# 555_Solar_Wind.net
KiCad netlist of a schematic drawn in EAGLE
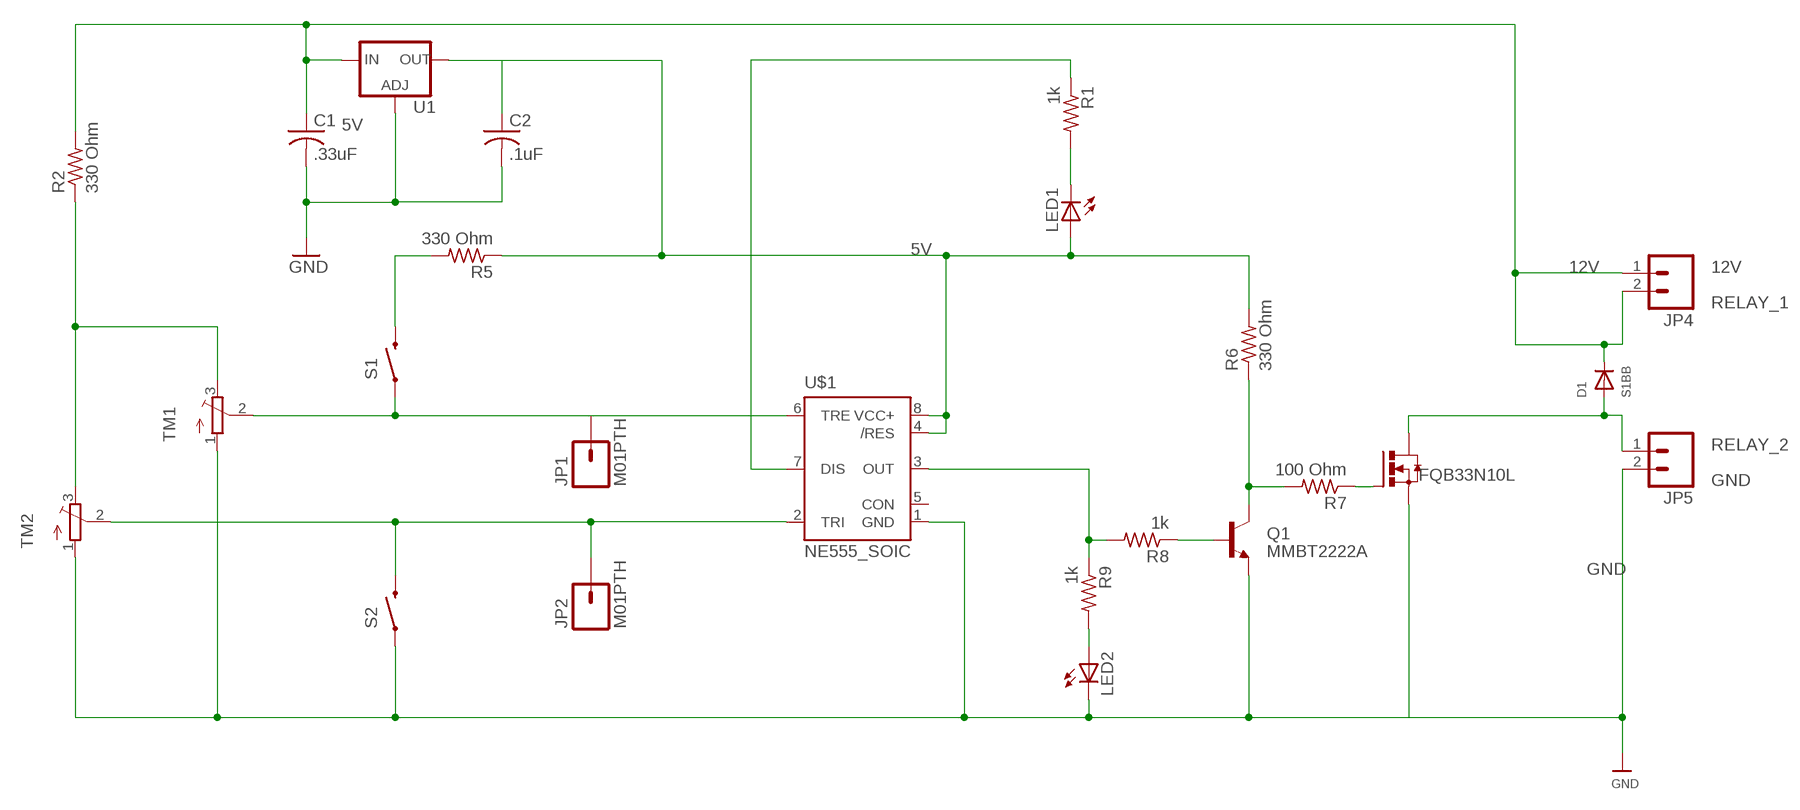
[diagram p0: schematic, sheet 1]

(export (version "E")
  (design (tool "Eeschema 10.0.6"))
  (components
    (comp (ref "C1")
      (value ".33uF")
      (footprint "eagle-import:C0805K")
      (libsource (lib "eagle-import") (part "C-USC0805K"))
    )
    (comp (ref "C2")
      (value ".1uF")
      (footprint "eagle-import:C0805K")
      (libsource (lib "eagle-import") (part "C-USC0805K"))
    )
    (comp (ref "D1")
      (value "S1BB")
      (footprint "eagle-import:SMADIODE")
      (libsource (lib "eagle-import") (part "DIODESMA"))
    )
    (comp (ref "JP1")
      (value "M01PTH")
      (footprint "eagle-import:1X01")
      (libsource (lib "eagle-import") (part "M01PTH"))
    )
    (comp (ref "JP2")
      (value "M01PTH")
      (footprint "eagle-import:1X01")
      (libsource (lib "eagle-import") (part "M01PTH"))
    )
    (comp (ref "JP4")
      (value "M023.5MM_LOCK")
      (footprint "eagle-import:SCREWTERMINAL-3.5MM-2_LOCK")
      (libsource (lib "eagle-import") (part "M023.5MM_LOCK"))
    )
    (comp (ref "JP5")
      (value "M023.5MM_LOCK")
      (footprint "eagle-import:SCREWTERMINAL-3.5MM-2_LOCK")
      (libsource (lib "eagle-import") (part "M023.5MM_LOCK"))
    )
    (comp (ref "LED1")
      (value "LEDCHIP-LED0603")
      (footprint "eagle-import:CHIP-LED0603")
      (libsource (lib "eagle-import") (part "LEDCHIP-LED0603"))
    )
    (comp (ref "LED2")
      (value "LEDCHIP-LED0603")
      (footprint "eagle-import:CHIP-LED0603")
      (libsource (lib "eagle-import") (part "LEDCHIP-LED0603"))
    )
    (comp (ref "Q1")
      (value "MMBT2222A")
      (footprint "eagle-import:SOT23")
      (libsource (lib "eagle-import") (part "TRANSISTOR_NPNMMBT2222A"))
    )
    (comp (ref "Q2")
      (value "FQB33N10L")
      (footprint "eagle-import:D2PACK")
      (libsource (lib "eagle-import") (part "IRF3704S"))
    )
    (comp (ref "R1")
      (value "1k")
      (footprint "eagle-import:M0805")
      (libsource (lib "eagle-import") (part "R-US_M0805"))
    )
    (comp (ref "R2")
      (value "330 Ohm")
      (footprint "eagle-import:M0805")
      (libsource (lib "eagle-import") (part "R-US_M0805"))
    )
    (comp (ref "R5")
      (value "330 Ohm")
      (footprint "eagle-import:M0805")
      (libsource (lib "eagle-import") (part "R-US_M0805"))
    )
    (comp (ref "R6")
      (value "330 Ohm")
      (footprint "eagle-import:M0805")
      (libsource (lib "eagle-import") (part "R-US_M0805"))
    )
    (comp (ref "R7")
      (value "100 Ohm")
      (footprint "eagle-import:M0805")
      (libsource (lib "eagle-import") (part "R-US_M0805"))
    )
    (comp (ref "R8")
      (value "1k")
      (footprint "eagle-import:M0805")
      (libsource (lib "eagle-import") (part "R-US_M0805"))
    )
    (comp (ref "R9")
      (value "1k")
      (footprint "eagle-import:M0805")
      (libsource (lib "eagle-import") (part "R-US_M0805"))
    )
    (comp (ref "S1")
      (value "SWITCH-MOMENTARY-2")
      (footprint "eagle-import:TACTILE_SWITCH_TALL")
      (libsource (lib "eagle-import") (part "SWITCH-MOMENTARY-2"))
    )
    (comp (ref "S2")
      (value "SWITCH-MOMENTARY-2")
      (footprint "eagle-import:TACTILE_SWITCH_TALL")
      (libsource (lib "eagle-import") (part "SWITCH-MOMENTARY-2"))
    )
    (comp (ref "TM1")
      (value "TRIMPOTTC33X")
      (footprint "eagle-import:TC33X")
      (libsource (lib "eagle-import") (part "TRIMPOTTC33X"))
    )
    (comp (ref "TM2")
      (value "TRIMPOTTC33X")
      (footprint "eagle-import:TC33X")
      (libsource (lib "eagle-import") (part "TRIMPOTTC33X"))
    )
    (comp (ref "U$1")
      (value "NE555_SOIC")
      (footprint "eagle-import:SO08")
      (libsource (lib "eagle-import") (part "NE555_SOIC"))
    )
    (comp (ref "U1")
      (value "5V")
      (footprint "eagle-import:SOT223")
      (libsource (lib "eagle-import") (part "V_REG_317SMD"))
    )
  )
  (nets
    (net (code "1") (name "/5V") (class "Default")
      (node (ref "C2") (pin "1") (pinfunction "1_1") (pintype "passive"))
      (node (ref "LED1") (pin "A") (pinfunction "A_A") (pintype "passive"))
      (node (ref "R5") (pin "1") (pinfunction "1_1") (pintype "passive"))
      (node (ref "R6") (pin "2") (pinfunction "2_2") (pintype "passive"))
      (node (ref "U$1") (pin "4") (pinfunction "/RES_4") (pintype "input"))
      (node (ref "U$1") (pin "8") (pinfunction "VCC+_8") (pintype "power_in"))
      (node (ref "U1") (pin "2") (pinfunction "OUT_2") (pintype "output"))
    )
    (net (code "2") (name "/12V") (class "Default")
      (node (ref "C1") (pin "1") (pinfunction "1_1") (pintype "passive"))
      (node (ref "D1") (pin "C") (pinfunction "C_C") (pintype "passive"))
      (node (ref "JP4") (pin "1") (pinfunction "1_1") (pintype "passive"))
      (node (ref "JP4") (pin "2") (pinfunction "2_2") (pintype "passive"))
      (node (ref "R2") (pin "2") (pinfunction "2_2") (pintype "passive"))
      (node (ref "U1") (pin "3") (pinfunction "IN_3") (pintype "input"))
    )
    (net (code "3") (name "GND") (class "Default")
      (node (ref "C1") (pin "2") (pinfunction "2_2") (pintype "passive"))
      (node (ref "C2") (pin "2") (pinfunction "2_2") (pintype "passive"))
      (node (ref "JP5") (pin "2") (pinfunction "2_2") (pintype "passive"))
      (node (ref "LED2") (pin "C") (pinfunction "C_C") (pintype "passive"))
      (node (ref "Q1") (pin "2") (pinfunction "E_2") (pintype "passive"))
      (node (ref "Q2") (pin "3") (pinfunction "S_3") (pintype "passive"))
      (node (ref "S2") (pin "A2") (pinfunction "1_A2") (pintype "passive"))
      (node (ref "TM1") (pin "1") (pinfunction "A_1") (pintype "passive"))
      (node (ref "TM2") (pin "1") (pinfunction "A_1") (pintype "passive"))
      (node (ref "U$1") (pin "1") (pinfunction "GND_1") (pintype "power_in"))
      (node (ref "U1") (pin "1") (pinfunction "ADJ_1") (pintype "input"))
    )
    (net (code "4") (name "Net-(LED1-PadC)") (class "Default")
      (node (ref "LED1") (pin "C") (pinfunction "C_C") (pintype "passive"))
      (node (ref "R1") (pin "2") (pinfunction "2_2") (pintype "passive"))
    )
    (net (code "5") (name "Net-(LED2-PadA)") (class "Default")
      (node (ref "LED2") (pin "A") (pinfunction "A_A") (pintype "passive"))
      (node (ref "R9") (pin "2") (pinfunction "2_2") (pintype "passive"))
    )
    (net (code "6") (name "Net-(Q1-B)") (class "Default")
      (node (ref "Q1") (pin "1") (pinfunction "B_1") (pintype "passive"))
      (node (ref "R8") (pin "1") (pinfunction "1_1") (pintype "passive"))
    )
    (net (code "7") (name "Net-(Q1-C)") (class "Default")
      (node (ref "Q1") (pin "3") (pinfunction "C_3") (pintype "passive"))
      (node (ref "R6") (pin "1") (pinfunction "1_1") (pintype "passive"))
      (node (ref "R7") (pin "2") (pinfunction "2_2") (pintype "passive"))
    )
    (net (code "8") (name "Net-(Q2-D)") (class "Default")
      (node (ref "D1") (pin "A") (pinfunction "A_A") (pintype "passive"))
      (node (ref "JP5") (pin "1") (pinfunction "1_1") (pintype "passive"))
      (node (ref "Q2") (pin "2") (pinfunction "D_2") (pintype "passive"))
    )
    (net (code "9") (name "Net-(Q2-G)") (class "Default")
      (node (ref "Q2") (pin "1") (pinfunction "G_1") (pintype "passive"))
      (node (ref "R7") (pin "1") (pinfunction "1_1") (pintype "passive"))
    )
    (net (code "10") (name "Net-(S1-1)") (class "Default")
      (node (ref "JP1") (pin "1") (pinfunction "1_1") (pintype "passive"))
      (node (ref "S1") (pin "A2") (pinfunction "1_A2") (pintype "passive"))
      (node (ref "TM1") (pin "2") (pinfunction "S_2") (pintype "passive"))
      (node (ref "U$1") (pin "6") (pinfunction "TRE_6") (pintype "input"))
    )
    (net (code "11") (name "Net-(S1-2)") (class "Default")
      (node (ref "R5") (pin "2") (pinfunction "2_2") (pintype "passive"))
      (node (ref "S1") (pin "B2") (pinfunction "2_B2") (pintype "passive"))
    )
    (net (code "12") (name "Net-(S2-2)") (class "Default")
      (node (ref "JP2") (pin "1") (pinfunction "1_1") (pintype "passive"))
      (node (ref "S2") (pin "B2") (pinfunction "2_B2") (pintype "passive"))
      (node (ref "TM2") (pin "2") (pinfunction "S_2") (pintype "passive"))
      (node (ref "U$1") (pin "2") (pinfunction "TRI_2") (pintype "input"))
    )
    (net (code "13") (name "Net-(TM1-E)") (class "Default")
      (node (ref "R2") (pin "1") (pinfunction "1_1") (pintype "passive"))
      (node (ref "TM1") (pin "3") (pinfunction "E_3") (pintype "passive"))
      (node (ref "TM2") (pin "3") (pinfunction "E_3") (pintype "passive"))
    )
    (net (code "14") (name "Net-(U$1-DIS)") (class "Default")
      (node (ref "R1") (pin "1") (pinfunction "1_1") (pintype "passive"))
      (node (ref "U$1") (pin "7") (pinfunction "DIS_7") (pintype "input"))
    )
    (net (code "15") (name "Net-(U$1-OUT)") (class "Default")
      (node (ref "R8") (pin "2") (pinfunction "2_2") (pintype "passive"))
      (node (ref "R9") (pin "1") (pinfunction "1_1") (pintype "passive"))
      (node (ref "U$1") (pin "3") (pinfunction "OUT_3") (pintype "output"))
    )
    (net (code "16") (name "unconnected-(U$1-CON-Pad5)") (class "Default")
      (node (ref "U$1") (pin "5") (pinfunction "CON_5") (pintype "input"))
    )
  )
)
